# V_1.net
KiCad netlist of a schematic drawn in Altium Designer
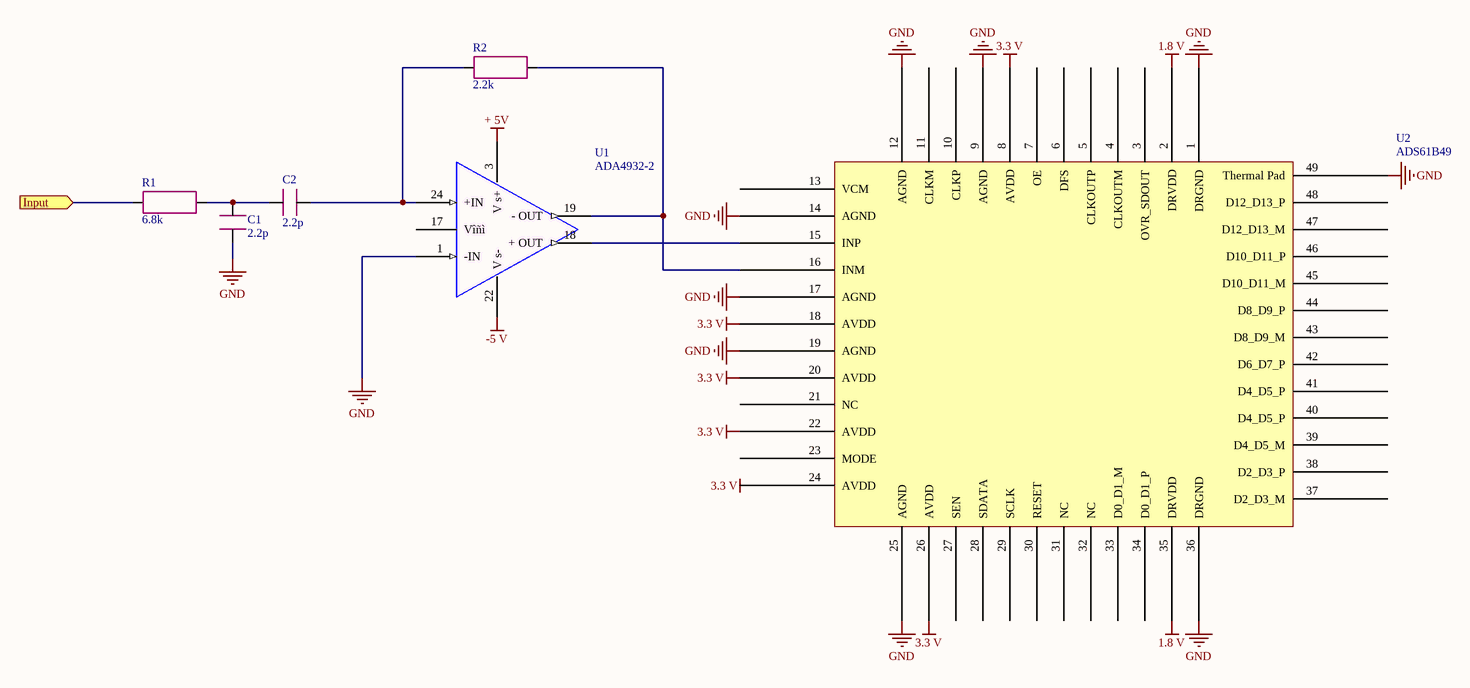
[diagram p0: V_1.SchDoc]

(export (version "E")
  (design (tool "Eeschema 10.0.6"))
  (components
    (comp (ref "C1") (value "2.2p") (footprint "V_1:C_0805") (libsource (lib "V_1") (part "C")))
    (comp (ref "C2") (value "2.2p") (footprint "V_1:C_0805") (libsource (lib "V_1") (part "C")))
    (comp (ref "R1") (value "6.8k") (footprint "V_1:R_0805") (libsource (lib "V_1") (part "R")))
    (comp (ref "R2") (value "2.2k") (footprint "V_1:R_0805") (libsource (lib "V_1") (part "R")))
    (comp (ref "U1")
      (value "ADA4932-2")
      (footprint "V_1:ADA4932-2")
      (libsource (lib "V_1") (part "ADA4932-2"))
    )
    (comp (ref "U2") (value "ADS61B49") (footprint "V_1:ADS61B49") (libsource (lib "V_1") (part "ADS61B49")))
  )
  (nets
    (net (code "1") (name "+ 5V") (class "Default")
      (node (ref "U1") (pin "3") (pinfunction "V_s+_3") (pintype "passive"))
    )
    (net (code "2") (name "-5 V") (class "Default")
      (node (ref "U1") (pin "22") (pinfunction "V_s-_22") (pintype "passive"))
    )
    (net (code "3") (name "/Input") (class "Default")
      (node (ref "R1") (pin "1") (pinfunction "1_1") (pintype "passive"))
    )
    (net (code "4") (name "1.8 V") (class "Default")
      (node (ref "U2") (pin "2") (pinfunction "DRVDD_2") (pintype "passive"))
      (node (ref "U2") (pin "35") (pinfunction "DRVDD_35") (pintype "passive"))
    )
    (net (code "5") (name "3.3 V") (class "Default")
      (node (ref "U2") (pin "18") (pinfunction "AVDD_18") (pintype "passive"))
      (node (ref "U2") (pin "20") (pinfunction "AVDD_20") (pintype "passive"))
      (node (ref "U2") (pin "22") (pinfunction "AVDD_22") (pintype "passive"))
      (node (ref "U2") (pin "26") (pinfunction "AVDD_26") (pintype "passive"))
      (node (ref "U2") (pin "8") (pinfunction "AVDD_8") (pintype "passive"))
    )
    (net (code "6") (name "GND") (class "Default")
      (node (ref "C1") (pin "1") (pinfunction "1_1") (pintype "passive"))
      (node (ref "U1") (pin "1") (pinfunction "-IN_1") (pintype "input"))
      (node (ref "U2") (pin "1") (pinfunction "DRGND_1") (pintype "passive"))
      (node (ref "U2") (pin "12") (pinfunction "AGND_12") (pintype "passive"))
      (node (ref "U2") (pin "14") (pinfunction "AGND_14") (pintype "passive"))
      (node (ref "U2") (pin "17") (pinfunction "AGND_17") (pintype "passive"))
      (node (ref "U2") (pin "19") (pinfunction "AGND_19") (pintype "passive"))
      (node (ref "U2") (pin "25") (pinfunction "AGND_25") (pintype "passive"))
      (node (ref "U2") (pin "36") (pinfunction "DRGND_36") (pintype "passive"))
      (node (ref "U2") (pin "49") (pinfunction "Thermal_Pad_49") (pintype "passive"))
      (node (ref "U2") (pin "9") (pinfunction "AGND_9") (pintype "passive"))
    )
    (net (code "7") (name "Net-(C1-Pad2)") (class "Default")
      (node (ref "C1") (pin "2") (pinfunction "2_2") (pintype "passive"))
      (node (ref "C2") (pin "1") (pinfunction "1_1") (pintype "passive"))
      (node (ref "R1") (pin "2") (pinfunction "2_2") (pintype "passive"))
    )
    (net (code "8") (name "Net-(U1-+IN)") (class "Default")
      (node (ref "C2") (pin "2") (pinfunction "2_2") (pintype "passive"))
      (node (ref "R2") (pin "1") (pinfunction "1_1") (pintype "passive"))
      (node (ref "U1") (pin "24") (pinfunction "+IN_24") (pintype "input"))
    )
    (net (code "9") (name "Net-(U1-+_OUT)") (class "Default")
      (node (ref "U1") (pin "18") (pinfunction "+_OUT_18") (pintype "output"))
      (node (ref "U2") (pin "15") (pinfunction "INP_15") (pintype "passive"))
    )
    (net (code "10") (name "Net-(U1--_OUT)") (class "Default")
      (node (ref "R2") (pin "2") (pinfunction "2_2") (pintype "passive"))
      (node (ref "U1") (pin "19") (pinfunction "-_OUT_19") (pintype "output"))
      (node (ref "U2") (pin "16") (pinfunction "INM_16") (pintype "passive"))
    )
    (net (code "11") (name "unconnected-(U1-Vîñì-Pad17)") (class "Default")
      (node (ref "U1") (pin "17") (pinfunction "Vîñì_17") (pintype "passive"))
    )
    (net (code "12") (name "unconnected-(U2-AVDD-Pad24)") (class "Default")
      (node (ref "U2") (pin "24") (pinfunction "AVDD_24") (pintype "passive"))
    )
    (net (code "13") (name "unconnected-(U2-CLKM-Pad11)") (class "Default")
      (node (ref "U2") (pin "11") (pinfunction "CLKM_11") (pintype "passive"))
    )
    (net (code "14") (name "unconnected-(U2-CLKOUTM-Pad4)") (class "Default")
      (node (ref "U2") (pin "4") (pinfunction "CLKOUTM_4") (pintype "passive"))
    )
    (net (code "15") (name "unconnected-(U2-CLKOUTP-Pad5)") (class "Default")
      (node (ref "U2") (pin "5") (pinfunction "CLKOUTP_5") (pintype "passive"))
    )
    (net (code "16") (name "unconnected-(U2-CLKP-Pad10)") (class "Default")
      (node (ref "U2") (pin "10") (pinfunction "CLKP_10") (pintype "passive"))
    )
    (net (code "17") (name "unconnected-(U2-D0_D1_M-Pad33)") (class "Default")
      (node (ref "U2") (pin "33") (pinfunction "D0_D1_M_33") (pintype "passive"))
    )
    (net (code "18") (name "unconnected-(U2-D0_D1_P-Pad34)") (class "Default")
      (node (ref "U2") (pin "34") (pinfunction "D0_D1_P_34") (pintype "passive"))
    )
    (net (code "19") (name "unconnected-(U2-D2_D3_M-Pad37)") (class "Default")
      (node (ref "U2") (pin "37") (pinfunction "D2_D3_M_37") (pintype "passive"))
    )
    (net (code "20") (name "unconnected-(U2-D2_D3_P-Pad38)") (class "Default")
      (node (ref "U2") (pin "38") (pinfunction "D2_D3_P_38") (pintype "passive"))
    )
    (net (code "21") (name "unconnected-(U2-D4_D5_M-Pad39)") (class "Default")
      (node (ref "U2") (pin "39") (pinfunction "D4_D5_M_39") (pintype "passive"))
    )
    (net (code "22") (name "unconnected-(U2-D4_D5_P-Pad40)") (class "Default")
      (node (ref "U2") (pin "40") (pinfunction "D4_D5_P_40") (pintype "passive"))
    )
    (net (code "23") (name "unconnected-(U2-D4_D5_P-Pad41)") (class "Default")
      (node (ref "U2") (pin "41") (pinfunction "D4_D5_P_41") (pintype "passive"))
    )
    (net (code "24") (name "unconnected-(U2-D6_D7_P-Pad42)") (class "Default")
      (node (ref "U2") (pin "42") (pinfunction "D6_D7_P_42") (pintype "passive"))
    )
    (net (code "25") (name "unconnected-(U2-D8_D9_M-Pad43)") (class "Default")
      (node (ref "U2") (pin "43") (pinfunction "D8_D9_M_43") (pintype "passive"))
    )
    (net (code "26") (name "unconnected-(U2-D8_D9_P-Pad44)") (class "Default")
      (node (ref "U2") (pin "44") (pinfunction "D8_D9_P_44") (pintype "passive"))
    )
    (net (code "27") (name "unconnected-(U2-D10_D11_M-Pad45)") (class "Default")
      (node (ref "U2") (pin "45") (pinfunction "D10_D11_M_45") (pintype "passive"))
    )
    (net (code "28") (name "unconnected-(U2-D10_D11_P-Pad46)") (class "Default")
      (node (ref "U2") (pin "46") (pinfunction "D10_D11_P_46") (pintype "passive"))
    )
    (net (code "29") (name "unconnected-(U2-D12_D13_M-Pad47)") (class "Default")
      (node (ref "U2") (pin "47") (pinfunction "D12_D13_M_47") (pintype "passive"))
    )
    (net (code "30") (name "unconnected-(U2-D12_D13_P-Pad48)") (class "Default")
      (node (ref "U2") (pin "48") (pinfunction "D12_D13_P_48") (pintype "passive"))
    )
    (net (code "31") (name "unconnected-(U2-DFS-Pad6)") (class "Default")
      (node (ref "U2") (pin "6") (pinfunction "DFS_6") (pintype "passive"))
    )
    (net (code "32") (name "unconnected-(U2-MODE-Pad23)") (class "Default")
      (node (ref "U2") (pin "23") (pinfunction "MODE_23") (pintype "passive"))
    )
    (net (code "33") (name "unconnected-(U2-NC-Pad21)") (class "Default")
      (node (ref "U2") (pin "21") (pinfunction "NC_21") (pintype "passive"))
    )
    (net (code "34") (name "unconnected-(U2-NC-Pad31)") (class "Default")
      (node (ref "U2") (pin "31") (pinfunction "NC_31") (pintype "passive"))
    )
    (net (code "35") (name "unconnected-(U2-NC-Pad32)") (class "Default")
      (node (ref "U2") (pin "32") (pinfunction "NC_32") (pintype "passive"))
    )
    (net (code "36") (name "unconnected-(U2-OE-Pad7)") (class "Default")
      (node (ref "U2") (pin "7") (pinfunction "OE_7") (pintype "passive"))
    )
    (net (code "37") (name "unconnected-(U2-OVR_SDOUT-Pad3)") (class "Default")
      (node (ref "U2") (pin "3") (pinfunction "OVR_SDOUT_3") (pintype "passive"))
    )
    (net (code "38") (name "unconnected-(U2-RESET-Pad30)") (class "Default")
      (node (ref "U2") (pin "30") (pinfunction "RESET_30") (pintype "passive"))
    )
    (net (code "39") (name "unconnected-(U2-SCLK-Pad29)") (class "Default")
      (node (ref "U2") (pin "29") (pinfunction "SCLK_29") (pintype "passive"))
    )
    (net (code "40") (name "unconnected-(U2-SDATA-Pad28)") (class "Default")
      (node (ref "U2") (pin "28") (pinfunction "SDATA_28") (pintype "passive"))
    )
    (net (code "41") (name "unconnected-(U2-SEN-Pad27)") (class "Default")
      (node (ref "U2") (pin "27") (pinfunction "SEN_27") (pintype "passive"))
    )
    (net (code "42") (name "unconnected-(U2-VCM-Pad13)") (class "Default")
      (node (ref "U2") (pin "13") (pinfunction "VCM_13") (pintype "passive"))
    )
  )
)
